# PGTNX07_gate_out.net
KiCad netlist of a schematic drawn in EAGLE
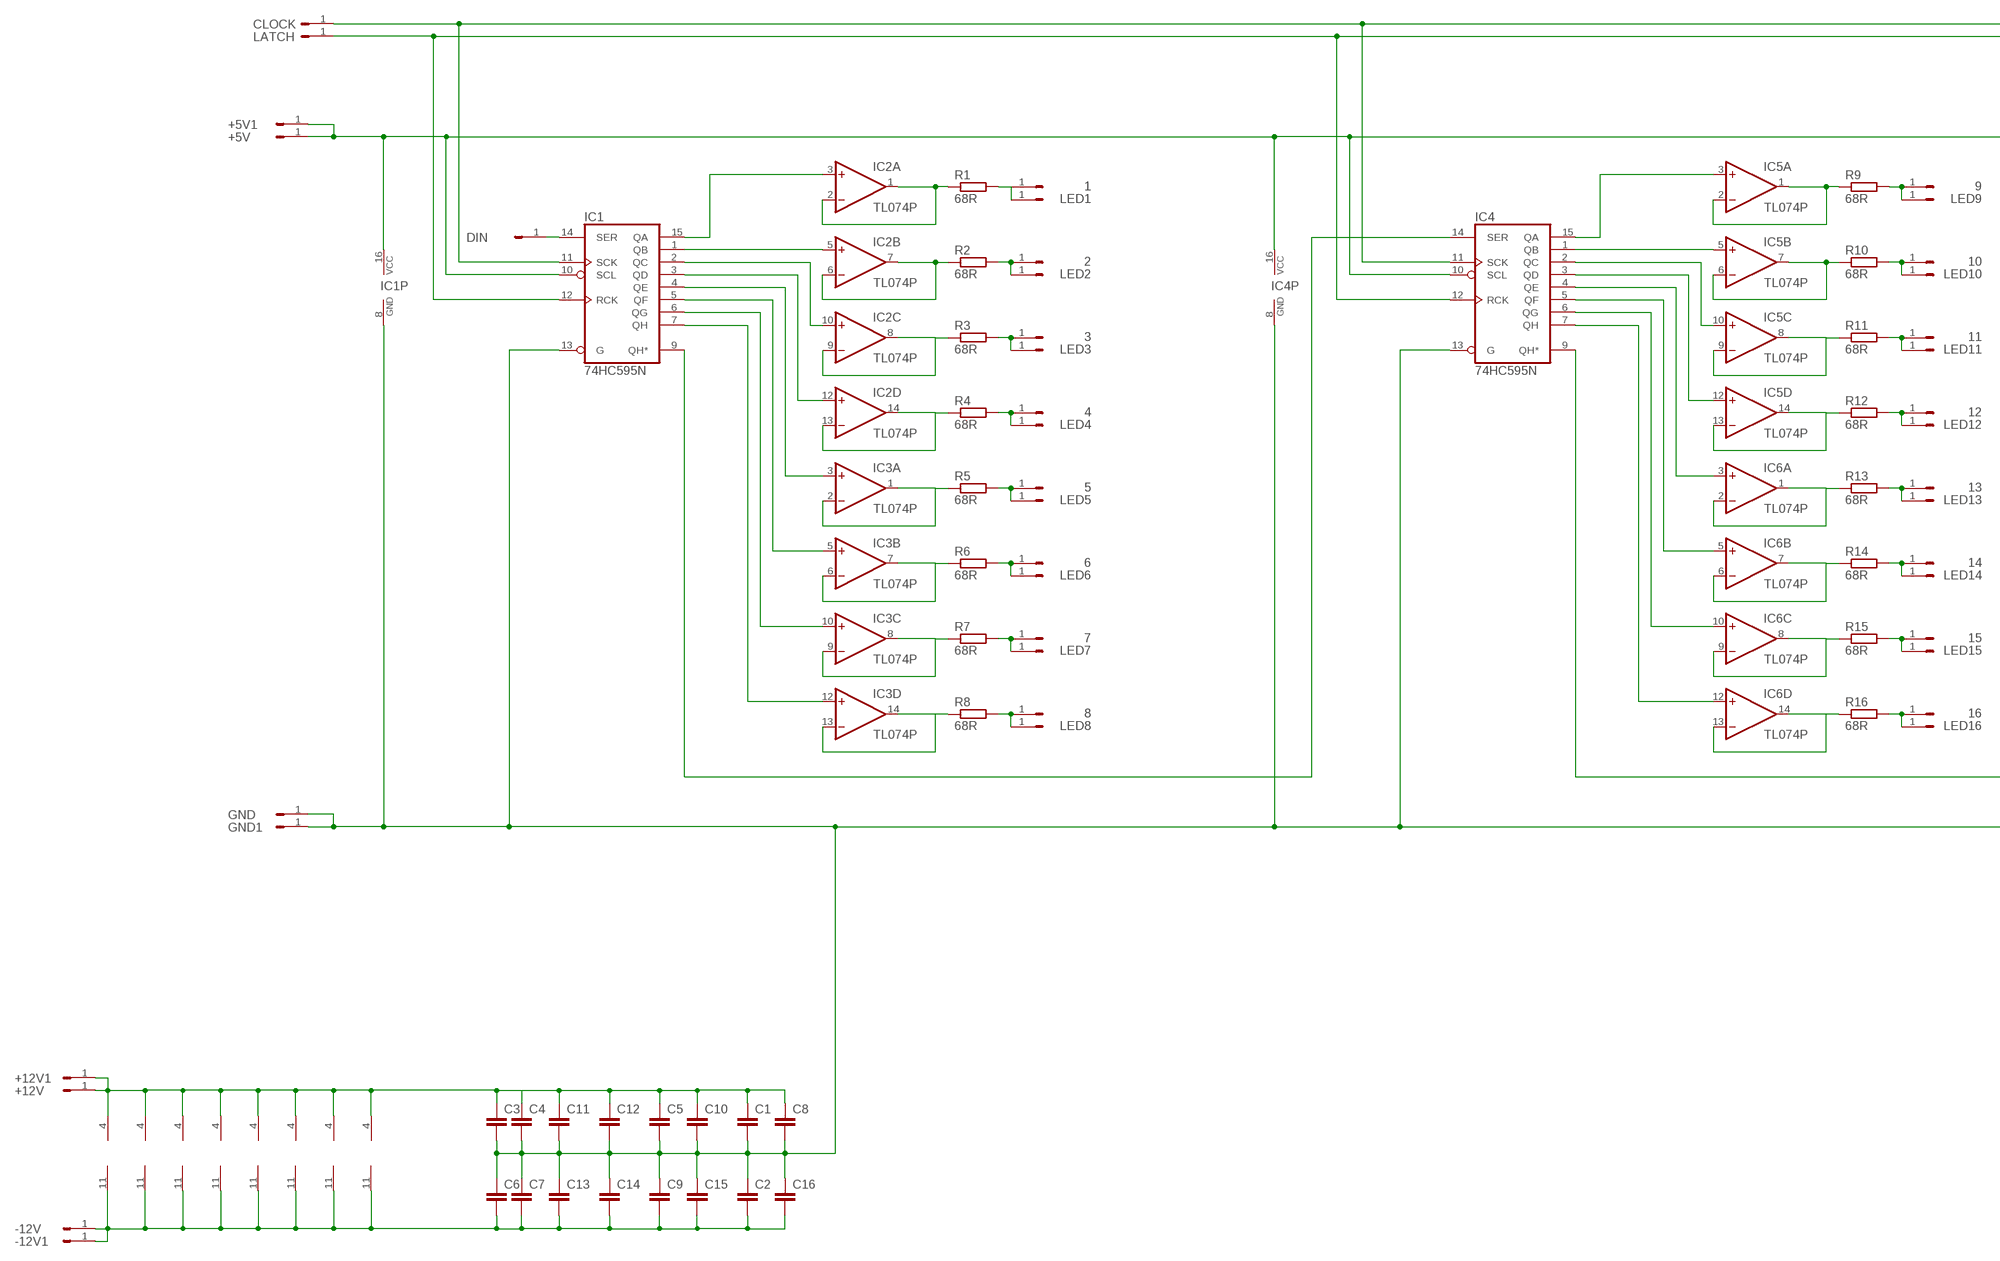
[diagram p0: schematic, sheet 1, part 1 of 2]
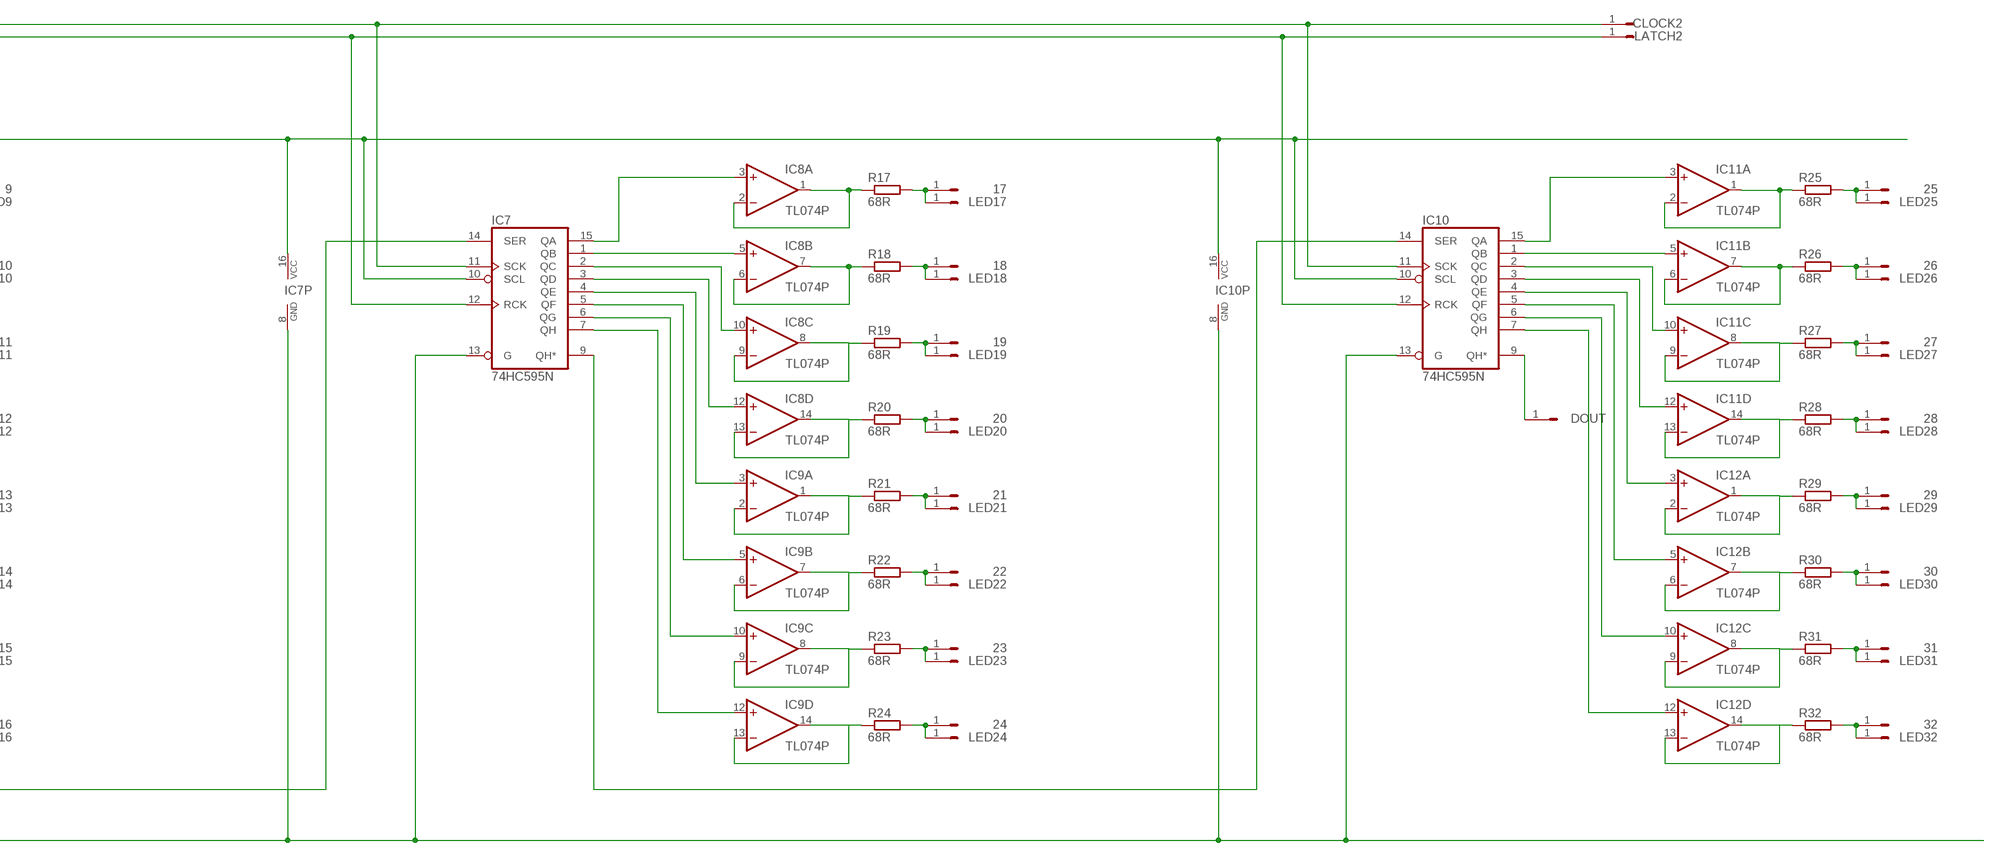
[diagram p1: schematic, sheet 1, part 2 of 2]

(export (version "E")
  (design (tool "Eeschema 10.0.6"))
  (components
    (comp (ref "+5V")
      (value "HEADER/MALE/01")
      (footprint "eagle-import:HEADER_MALE_01")
      (libsource (lib "eagle-import") (part "HEADER/MALE/01"))
    )
    (comp (ref "+5V1")
      (value "HEADER/MALE/01")
      (footprint "eagle-import:HEADER_MALE_01")
      (libsource (lib "eagle-import") (part "HEADER/MALE/01"))
    )
    (comp (ref "+12V")
      (value "HEADER/MALE/01")
      (footprint "eagle-import:HEADER_MALE_01")
      (libsource (lib "eagle-import") (part "HEADER/MALE/01"))
    )
    (comp (ref "+12V1")
      (value "HEADER/MALE/01")
      (footprint "eagle-import:HEADER_MALE_01")
      (libsource (lib "eagle-import") (part "HEADER/MALE/01"))
    )
    (comp (ref "-12V")
      (value "HEADER/MALE/01")
      (footprint "eagle-import:HEADER_MALE_01")
      (libsource (lib "eagle-import") (part "HEADER/MALE/01"))
    )
    (comp (ref "-12V1")
      (value "HEADER/MALE/01")
      (footprint "eagle-import:HEADER_MALE_01")
      (libsource (lib "eagle-import") (part "HEADER/MALE/01"))
    )
    (comp (ref "1")
      (value "HEADER/MALE/01")
      (footprint "eagle-import:HEADER_MALE_01")
      (libsource (lib "eagle-import") (part "HEADER/MALE/01"))
    )
    (comp (ref "2")
      (value "HEADER/MALE/01")
      (footprint "eagle-import:HEADER_MALE_01")
      (libsource (lib "eagle-import") (part "HEADER/MALE/01"))
    )
    (comp (ref "3")
      (value "HEADER/MALE/01")
      (footprint "eagle-import:HEADER_MALE_01")
      (libsource (lib "eagle-import") (part "HEADER/MALE/01"))
    )
    (comp (ref "4")
      (value "HEADER/MALE/01")
      (footprint "eagle-import:HEADER_MALE_01")
      (libsource (lib "eagle-import") (part "HEADER/MALE/01"))
    )
    (comp (ref "5")
      (value "HEADER/MALE/01")
      (footprint "eagle-import:HEADER_MALE_01")
      (libsource (lib "eagle-import") (part "HEADER/MALE/01"))
    )
    (comp (ref "6")
      (value "HEADER/MALE/01")
      (footprint "eagle-import:HEADER_MALE_01")
      (libsource (lib "eagle-import") (part "HEADER/MALE/01"))
    )
    (comp (ref "7")
      (value "HEADER/MALE/01")
      (footprint "eagle-import:HEADER_MALE_01")
      (libsource (lib "eagle-import") (part "HEADER/MALE/01"))
    )
    (comp (ref "8")
      (value "HEADER/MALE/01")
      (footprint "eagle-import:HEADER_MALE_01")
      (libsource (lib "eagle-import") (part "HEADER/MALE/01"))
    )
    (comp (ref "9")
      (value "HEADER/MALE/01")
      (footprint "eagle-import:HEADER_MALE_01")
      (libsource (lib "eagle-import") (part "HEADER/MALE/01"))
    )
    (comp (ref "10")
      (value "HEADER/MALE/01")
      (footprint "eagle-import:HEADER_MALE_01")
      (libsource (lib "eagle-import") (part "HEADER/MALE/01"))
    )
    (comp (ref "11")
      (value "HEADER/MALE/01")
      (footprint "eagle-import:HEADER_MALE_01")
      (libsource (lib "eagle-import") (part "HEADER/MALE/01"))
    )
    (comp (ref "12")
      (value "HEADER/MALE/01")
      (footprint "eagle-import:HEADER_MALE_01")
      (libsource (lib "eagle-import") (part "HEADER/MALE/01"))
    )
    (comp (ref "13")
      (value "HEADER/MALE/01")
      (footprint "eagle-import:HEADER_MALE_01")
      (libsource (lib "eagle-import") (part "HEADER/MALE/01"))
    )
    (comp (ref "14")
      (value "HEADER/MALE/01")
      (footprint "eagle-import:HEADER_MALE_01")
      (libsource (lib "eagle-import") (part "HEADER/MALE/01"))
    )
    (comp (ref "15")
      (value "HEADER/MALE/01")
      (footprint "eagle-import:HEADER_MALE_01")
      (libsource (lib "eagle-import") (part "HEADER/MALE/01"))
    )
    (comp (ref "16")
      (value "HEADER/MALE/01")
      (footprint "eagle-import:HEADER_MALE_01")
      (libsource (lib "eagle-import") (part "HEADER/MALE/01"))
    )
    (comp (ref "17")
      (value "HEADER/MALE/01")
      (footprint "eagle-import:HEADER_MALE_01")
      (libsource (lib "eagle-import") (part "HEADER/MALE/01"))
    )
    (comp (ref "18")
      (value "HEADER/MALE/01")
      (footprint "eagle-import:HEADER_MALE_01")
      (libsource (lib "eagle-import") (part "HEADER/MALE/01"))
    )
    (comp (ref "19")
      (value "HEADER/MALE/01")
      (footprint "eagle-import:HEADER_MALE_01")
      (libsource (lib "eagle-import") (part "HEADER/MALE/01"))
    )
    (comp (ref "20")
      (value "HEADER/MALE/01")
      (footprint "eagle-import:HEADER_MALE_01")
      (libsource (lib "eagle-import") (part "HEADER/MALE/01"))
    )
    (comp (ref "21")
      (value "HEADER/MALE/01")
      (footprint "eagle-import:HEADER_MALE_01")
      (libsource (lib "eagle-import") (part "HEADER/MALE/01"))
    )
    (comp (ref "22")
      (value "HEADER/MALE/01")
      (footprint "eagle-import:HEADER_MALE_01")
      (libsource (lib "eagle-import") (part "HEADER/MALE/01"))
    )
    (comp (ref "23")
      (value "HEADER/MALE/01")
      (footprint "eagle-import:HEADER_MALE_01")
      (libsource (lib "eagle-import") (part "HEADER/MALE/01"))
    )
    (comp (ref "24")
      (value "HEADER/MALE/01")
      (footprint "eagle-import:HEADER_MALE_01")
      (libsource (lib "eagle-import") (part "HEADER/MALE/01"))
    )
    (comp (ref "25")
      (value "HEADER/MALE/01")
      (footprint "eagle-import:HEADER_MALE_01")
      (libsource (lib "eagle-import") (part "HEADER/MALE/01"))
    )
    (comp (ref "26")
      (value "HEADER/MALE/01")
      (footprint "eagle-import:HEADER_MALE_01")
      (libsource (lib "eagle-import") (part "HEADER/MALE/01"))
    )
    (comp (ref "27")
      (value "HEADER/MALE/01")
      (footprint "eagle-import:HEADER_MALE_01")
      (libsource (lib "eagle-import") (part "HEADER/MALE/01"))
    )
    (comp (ref "28")
      (value "HEADER/MALE/01")
      (footprint "eagle-import:HEADER_MALE_01")
      (libsource (lib "eagle-import") (part "HEADER/MALE/01"))
    )
    (comp (ref "29")
      (value "HEADER/MALE/01")
      (footprint "eagle-import:HEADER_MALE_01")
      (libsource (lib "eagle-import") (part "HEADER/MALE/01"))
    )
    (comp (ref "30")
      (value "HEADER/MALE/01")
      (footprint "eagle-import:HEADER_MALE_01")
      (libsource (lib "eagle-import") (part "HEADER/MALE/01"))
    )
    (comp (ref "31")
      (value "HEADER/MALE/01")
      (footprint "eagle-import:HEADER_MALE_01")
      (libsource (lib "eagle-import") (part "HEADER/MALE/01"))
    )
    (comp (ref "32")
      (value "HEADER/MALE/01")
      (footprint "eagle-import:HEADER_MALE_01")
      (libsource (lib "eagle-import") (part "HEADER/MALE/01"))
    )
    (comp (ref "C1")
      (value "CAPACITORCERAMICDISC/5")
      (footprint "eagle-import:CERAMICDISC_5")
      (libsource (lib "eagle-import") (part "CAPACITORCERAMICDISC/5"))
    )
    (comp (ref "C2")
      (value "CAPACITORCERAMICDISC/5")
      (footprint "eagle-import:CERAMICDISC_5")
      (libsource (lib "eagle-import") (part "CAPACITORCERAMICDISC/5"))
    )
    (comp (ref "C3")
      (value "CAPACITORCERAMICDISC/5")
      (footprint "eagle-import:CERAMICDISC_5")
      (libsource (lib "eagle-import") (part "CAPACITORCERAMICDISC/5"))
    )
    (comp (ref "C4")
      (value "CAPACITORCERAMICDISC/5")
      (footprint "eagle-import:CERAMICDISC_5")
      (libsource (lib "eagle-import") (part "CAPACITORCERAMICDISC/5"))
    )
    (comp (ref "C5")
      (value "CAPACITORCERAMICDISC/5")
      (footprint "eagle-import:CERAMICDISC_5")
      (libsource (lib "eagle-import") (part "CAPACITORCERAMICDISC/5"))
    )
    (comp (ref "C6")
      (value "CAPACITORCERAMICDISC/5")
      (footprint "eagle-import:CERAMICDISC_5")
      (libsource (lib "eagle-import") (part "CAPACITORCERAMICDISC/5"))
    )
    (comp (ref "C7")
      (value "CAPACITORCERAMICDISC/5")
      (footprint "eagle-import:CERAMICDISC_5")
      (libsource (lib "eagle-import") (part "CAPACITORCERAMICDISC/5"))
    )
    (comp (ref "C8")
      (value "CAPACITORCERAMICDISC/5")
      (footprint "eagle-import:CERAMICDISC_5")
      (libsource (lib "eagle-import") (part "CAPACITORCERAMICDISC/5"))
    )
    (comp (ref "C9")
      (value "CAPACITORCERAMICDISC/5")
      (footprint "eagle-import:CERAMICDISC_5")
      (libsource (lib "eagle-import") (part "CAPACITORCERAMICDISC/5"))
    )
    (comp (ref "C10")
      (value "CAPACITORCERAMICDISC/5")
      (footprint "eagle-import:CERAMICDISC_5")
      (libsource (lib "eagle-import") (part "CAPACITORCERAMICDISC/5"))
    )
    (comp (ref "C11")
      (value "CAPACITORCERAMICDISC/5")
      (footprint "eagle-import:CERAMICDISC_5")
      (libsource (lib "eagle-import") (part "CAPACITORCERAMICDISC/5"))
    )
    (comp (ref "C12")
      (value "CAPACITORCERAMICDISC/5")
      (footprint "eagle-import:CERAMICDISC_5")
      (libsource (lib "eagle-import") (part "CAPACITORCERAMICDISC/5"))
    )
    (comp (ref "C13")
      (value "CAPACITORCERAMICDISC/5")
      (footprint "eagle-import:CERAMICDISC_5")
      (libsource (lib "eagle-import") (part "CAPACITORCERAMICDISC/5"))
    )
    (comp (ref "C14")
      (value "CAPACITORCERAMICDISC/5")
      (footprint "eagle-import:CERAMICDISC_5")
      (libsource (lib "eagle-import") (part "CAPACITORCERAMICDISC/5"))
    )
    (comp (ref "C15")
      (value "CAPACITORCERAMICDISC/5")
      (footprint "eagle-import:CERAMICDISC_5")
      (libsource (lib "eagle-import") (part "CAPACITORCERAMICDISC/5"))
    )
    (comp (ref "C16")
      (value "CAPACITORCERAMICDISC/5")
      (footprint "eagle-import:CERAMICDISC_5")
      (libsource (lib "eagle-import") (part "CAPACITORCERAMICDISC/5"))
    )
    (comp (ref "CLOCK")
      (value "HEADER/MALE/01")
      (footprint "eagle-import:HEADER_MALE_01")
      (libsource (lib "eagle-import") (part "HEADER/MALE/01"))
    )
    (comp (ref "CLOCK2")
      (value "HEADER/MALE/01")
      (footprint "eagle-import:HEADER_MALE_01")
      (libsource (lib "eagle-import") (part "HEADER/MALE/01"))
    )
    (comp (ref "DIN")
      (value "HEADER/MALE/01")
      (footprint "eagle-import:HEADER_MALE_01")
      (libsource (lib "eagle-import") (part "HEADER/MALE/01"))
    )
    (comp (ref "DOUT")
      (value "HEADER/MALE/01")
      (footprint "eagle-import:HEADER_MALE_01")
      (libsource (lib "eagle-import") (part "HEADER/MALE/01"))
    )
    (comp (ref "GND")
      (value "HEADER/MALE/01")
      (footprint "eagle-import:HEADER_MALE_01")
      (libsource (lib "eagle-import") (part "HEADER/MALE/01"))
    )
    (comp (ref "GND1")
      (value "HEADER/MALE/01")
      (footprint "eagle-import:HEADER_MALE_01")
      (libsource (lib "eagle-import") (part "HEADER/MALE/01"))
    )
    (comp (ref "IC1")
      (value "74HC595N")
      (footprint "eagle-import:DIL16")
      (libsource (lib "eagle-import") (part "74595NHC"))
    )
    (comp (ref "IC2")
      (value "TL074P")
      (footprint "eagle-import:DIL14")
      (libsource (lib "eagle-import") (part "TL074P"))
    )
    (comp (ref "IC3")
      (value "TL074P")
      (footprint "eagle-import:DIL14")
      (libsource (lib "eagle-import") (part "TL074P"))
    )
    (comp (ref "IC4")
      (value "74HC595N")
      (footprint "eagle-import:DIL16")
      (libsource (lib "eagle-import") (part "74595NHC"))
    )
    (comp (ref "IC5")
      (value "TL074P")
      (footprint "eagle-import:DIL14")
      (libsource (lib "eagle-import") (part "TL074P"))
    )
    (comp (ref "IC6")
      (value "TL074P")
      (footprint "eagle-import:DIL14")
      (libsource (lib "eagle-import") (part "TL074P"))
    )
    (comp (ref "IC7")
      (value "74HC595N")
      (footprint "eagle-import:DIL16")
      (libsource (lib "eagle-import") (part "74595NHC"))
    )
    (comp (ref "IC8")
      (value "TL074P")
      (footprint "eagle-import:DIL14")
      (libsource (lib "eagle-import") (part "TL074P"))
    )
    (comp (ref "IC9")
      (value "TL074P")
      (footprint "eagle-import:DIL14")
      (libsource (lib "eagle-import") (part "TL074P"))
    )
    (comp (ref "IC10")
      (value "74HC595N")
      (footprint "eagle-import:DIL16")
      (libsource (lib "eagle-import") (part "74595NHC"))
    )
    (comp (ref "IC11")
      (value "TL074P")
      (footprint "eagle-import:DIL14")
      (libsource (lib "eagle-import") (part "TL074P"))
    )
    (comp (ref "IC12")
      (value "TL074P")
      (footprint "eagle-import:DIL14")
      (libsource (lib "eagle-import") (part "TL074P"))
    )
    (comp (ref "LATCH")
      (value "HEADER/MALE/01")
      (footprint "eagle-import:HEADER_MALE_01")
      (libsource (lib "eagle-import") (part "HEADER/MALE/01"))
    )
    (comp (ref "LATCH2")
      (value "HEADER/MALE/01")
      (footprint "eagle-import:HEADER_MALE_01")
      (libsource (lib "eagle-import") (part "HEADER/MALE/01"))
    )
    (comp (ref "LED1")
      (value "HEADER/MALE/01")
      (footprint "eagle-import:HEADER_MALE_01")
      (libsource (lib "eagle-import") (part "HEADER/MALE/01"))
    )
    (comp (ref "LED2")
      (value "HEADER/MALE/01")
      (footprint "eagle-import:HEADER_MALE_01")
      (libsource (lib "eagle-import") (part "HEADER/MALE/01"))
    )
    (comp (ref "LED3")
      (value "HEADER/MALE/01")
      (footprint "eagle-import:HEADER_MALE_01")
      (libsource (lib "eagle-import") (part "HEADER/MALE/01"))
    )
    (comp (ref "LED4")
      (value "HEADER/MALE/01")
      (footprint "eagle-import:HEADER_MALE_01")
      (libsource (lib "eagle-import") (part "HEADER/MALE/01"))
    )
    (comp (ref "LED5")
      (value "HEADER/MALE/01")
      (footprint "eagle-import:HEADER_MALE_01")
      (libsource (lib "eagle-import") (part "HEADER/MALE/01"))
    )
    (comp (ref "LED6")
      (value "HEADER/MALE/01")
      (footprint "eagle-import:HEADER_MALE_01")
      (libsource (lib "eagle-import") (part "HEADER/MALE/01"))
    )
    (comp (ref "LED7")
      (value "HEADER/MALE/01")
      (footprint "eagle-import:HEADER_MALE_01")
      (libsource (lib "eagle-import") (part "HEADER/MALE/01"))
    )
    (comp (ref "LED8")
      (value "HEADER/MALE/01")
      (footprint "eagle-import:HEADER_MALE_01")
      (libsource (lib "eagle-import") (part "HEADER/MALE/01"))
    )
    (comp (ref "LED9")
      (value "HEADER/MALE/01")
      (footprint "eagle-import:HEADER_MALE_01")
      (libsource (lib "eagle-import") (part "HEADER/MALE/01"))
    )
    (comp (ref "LED10")
      (value "HEADER/MALE/01")
      (footprint "eagle-import:HEADER_MALE_01")
      (libsource (lib "eagle-import") (part "HEADER/MALE/01"))
    )
    (comp (ref "LED11")
      (value "HEADER/MALE/01")
      (footprint "eagle-import:HEADER_MALE_01")
      (libsource (lib "eagle-import") (part "HEADER/MALE/01"))
    )
    (comp (ref "LED12")
      (value "HEADER/MALE/01")
      (footprint "eagle-import:HEADER_MALE_01")
      (libsource (lib "eagle-import") (part "HEADER/MALE/01"))
    )
    (comp (ref "LED13")
      (value "HEADER/MALE/01")
      (footprint "eagle-import:HEADER_MALE_01")
      (libsource (lib "eagle-import") (part "HEADER/MALE/01"))
    )
    (comp (ref "LED14")
      (value "HEADER/MALE/01")
      (footprint "eagle-import:HEADER_MALE_01")
      (libsource (lib "eagle-import") (part "HEADER/MALE/01"))
    )
    (comp (ref "LED15")
      (value "HEADER/MALE/01")
      (footprint "eagle-import:HEADER_MALE_01")
      (libsource (lib "eagle-import") (part "HEADER/MALE/01"))
    )
    (comp (ref "LED16")
      (value "HEADER/MALE/01")
      (footprint "eagle-import:HEADER_MALE_01")
      (libsource (lib "eagle-import") (part "HEADER/MALE/01"))
    )
    (comp (ref "LED17")
      (value "HEADER/MALE/01")
      (footprint "eagle-import:HEADER_MALE_01")
      (libsource (lib "eagle-import") (part "HEADER/MALE/01"))
    )
    (comp (ref "LED18")
      (value "HEADER/MALE/01")
      (footprint "eagle-import:HEADER_MALE_01")
      (libsource (lib "eagle-import") (part "HEADER/MALE/01"))
    )
    (comp (ref "LED19")
      (value "HEADER/MALE/01")
      (footprint "eagle-import:HEADER_MALE_01")
      (libsource (lib "eagle-import") (part "HEADER/MALE/01"))
    )
    (comp (ref "LED20")
      (value "HEADER/MALE/01")
      (footprint "eagle-import:HEADER_MALE_01")
      (libsource (lib "eagle-import") (part "HEADER/MALE/01"))
    )
    (comp (ref "LED21")
      (value "HEADER/MALE/01")
      (footprint "eagle-import:HEADER_MALE_01")
      (libsource (lib "eagle-import") (part "HEADER/MALE/01"))
    )
    (comp (ref "LED22")
      (value "HEADER/MALE/01")
      (footprint "eagle-import:HEADER_MALE_01")
      (libsource (lib "eagle-import") (part "HEADER/MALE/01"))
    )
    (comp (ref "LED23")
      (value "HEADER/MALE/01")
      (footprint "eagle-import:HEADER_MALE_01")
      (libsource (lib "eagle-import") (part "HEADER/MALE/01"))
    )
    (comp (ref "LED24")
      (value "HEADER/MALE/01")
      (footprint "eagle-import:HEADER_MALE_01")
      (libsource (lib "eagle-import") (part "HEADER/MALE/01"))
    )
    (comp (ref "LED25")
      (value "HEADER/MALE/01")
      (footprint "eagle-import:HEADER_MALE_01")
      (libsource (lib "eagle-import") (part "HEADER/MALE/01"))
    )
    (comp (ref "LED26")
      (value "HEADER/MALE/01")
      (footprint "eagle-import:HEADER_MALE_01")
      (libsource (lib "eagle-import") (part "HEADER/MALE/01"))
    )
    (comp (ref "LED27")
      (value "HEADER/MALE/01")
      (footprint "eagle-import:HEADER_MALE_01")
      (libsource (lib "eagle-import") (part "HEADER/MALE/01"))
    )
    (comp (ref "LED28")
      (value "HEADER/MALE/01")
      (footprint "eagle-import:HEADER_MALE_01")
      (libsource (lib "eagle-import") (part "HEADER/MALE/01"))
    )
    (comp (ref "LED29")
      (value "HEADER/MALE/01")
      (footprint "eagle-import:HEADER_MALE_01")
      (libsource (lib "eagle-import") (part "HEADER/MALE/01"))
    )
    (comp (ref "LED30")
      (value "HEADER/MALE/01")
      (footprint "eagle-import:HEADER_MALE_01")
      (libsource (lib "eagle-import") (part "HEADER/MALE/01"))
    )
    (comp (ref "LED31")
      (value "HEADER/MALE/01")
      (footprint "eagle-import:HEADER_MALE_01")
      (libsource (lib "eagle-import") (part "HEADER/MALE/01"))
    )
    (comp (ref "LED32")
      (value "HEADER/MALE/01")
      (footprint "eagle-import:HEADER_MALE_01")
      (libsource (lib "eagle-import") (part "HEADER/MALE/01"))
    )
    (comp (ref "R1")
      (value "68R")
      (footprint "eagle-import:RESISTOR_7.5")
      (libsource (lib "eagle-import") (part "RESISTORRESISTOR/UPRIGHT/7.5"))
    )
    (comp (ref "R2")
      (value "68R")
      (footprint "eagle-import:RESISTOR_7.5")
      (libsource (lib "eagle-import") (part "RESISTORRESISTOR/UPRIGHT/7.5"))
    )
    (comp (ref "R3")
      (value "68R")
      (footprint "eagle-import:RESISTOR_7.5")
      (libsource (lib "eagle-import") (part "RESISTORRESISTOR/UPRIGHT/7.5"))
    )
    (comp (ref "R4")
      (value "68R")
      (footprint "eagle-import:RESISTOR_7.5")
      (libsource (lib "eagle-import") (part "RESISTORRESISTOR/UPRIGHT/7.5"))
    )
    (comp (ref "R5")
      (value "68R")
      (footprint "eagle-import:RESISTOR_7.5")
      (libsource (lib "eagle-import") (part "RESISTORRESISTOR/UPRIGHT/7.5"))
    )
    (comp (ref "R6")
      (value "68R")
      (footprint "eagle-import:RESISTOR_7.5")
      (libsource (lib "eagle-import") (part "RESISTORRESISTOR/UPRIGHT/7.5"))
    )
    (comp (ref "R7")
      (value "68R")
      (footprint "eagle-import:RESISTOR_7.5")
      (libsource (lib "eagle-import") (part "RESISTORRESISTOR/UPRIGHT/7.5"))
    )
    (comp (ref "R8")
      (value "68R")
      (footprint "eagle-import:RESISTOR_7.5")
      (libsource (lib "eagle-import") (part "RESISTORRESISTOR/UPRIGHT/7.5"))
    )
    (comp (ref "R9")
      (value "68R")
      (footprint "eagle-import:RESISTOR_7.5")
      (libsource (lib "eagle-import") (part "RESISTORRESISTOR/UPRIGHT/7.5"))
    )
    (comp (ref "R10")
      (value "68R")
      (footprint "eagle-import:RESISTOR_7.5")
      (libsource (lib "eagle-import") (part "RESISTORRESISTOR/UPRIGHT/7.5"))
    )
    (comp (ref "R11")
      (value "68R")
      (footprint "eagle-import:RESISTOR_7.5")
      (libsource (lib "eagle-import") (part "RESISTORRESISTOR/UPRIGHT/7.5"))
    )
    (comp (ref "R12")
      (value "68R")
      (footprint "eagle-import:RESISTOR_7.5")
      (libsource (lib "eagle-import") (part "RESISTORRESISTOR/UPRIGHT/7.5"))
    )
    (comp (ref "R13")
      (value "68R")
      (footprint "eagle-import:RESISTOR_7.5")
      (libsource (lib "eagle-import") (part "RESISTORRESISTOR/UPRIGHT/7.5"))
    )
    (comp (ref "R14")
      (value "68R")
      (footprint "eagle-import:RESISTOR_7.5")
      (libsource (lib "eagle-import") (part "RESISTORRESISTOR/UPRIGHT/7.5"))
    )
    (comp (ref "R15")
      (value "68R")
      (footprint "eagle-import:RESISTOR_7.5")
      (libsource (lib "eagle-import") (part "RESISTORRESISTOR/UPRIGHT/7.5"))
    )
    (comp (ref "R16")
      (value "68R")
      (footprint "eagle-import:RESISTOR_7.5")
      (libsource (lib "eagle-import") (part "RESISTORRESISTOR/UPRIGHT/7.5"))
    )
    (comp (ref "R17")
      (value "68R")
      (footprint "eagle-import:RESISTOR_7.5")
      (libsource (lib "eagle-import") (part "RESISTORRESISTOR/UPRIGHT/7.5"))
    )
    (comp (ref "R18")
      (value "68R")
      (footprint "eagle-import:RESISTOR_7.5")
      (libsource (lib "eagle-import") (part "RESISTORRESISTOR/UPRIGHT/7.5"))
    )
    (comp (ref "R19")
      (value "68R")
      (footprint "eagle-import:RESISTOR_7.5")
      (libsource (lib "eagle-import") (part "RESISTORRESISTOR/UPRIGHT/7.5"))
    )
    (comp (ref "R20")
      (value "68R")
      (footprint "eagle-import:RESISTOR_7.5")
      (libsource (lib "eagle-import") (part "RESISTORRESISTOR/UPRIGHT/7.5"))
    )
    (comp (ref "R21")
      (value "68R")
      (footprint "eagle-import:RESISTOR_7.5")
      (libsource (lib "eagle-import") (part "RESISTORRESISTOR/UPRIGHT/7.5"))
    )
    (comp (ref "R22")
      (value "68R")
      (footprint "eagle-import:RESISTOR_7.5")
      (libsource (lib "eagle-import") (part "RESISTORRESISTOR/UPRIGHT/7.5"))
    )
    (comp (ref "R23")
      (value "68R")
      (footprint "eagle-import:RESISTOR_7.5")
      (libsource (lib "eagle-import") (part "RESISTORRESISTOR/UPRIGHT/7.5"))
    )
    (comp (ref "R24")
      (value "68R")
      (footprint "eagle-import:RESISTOR_7.5")
      (libsource (lib "eagle-import") (part "RESISTORRESISTOR/UPRIGHT/7.5"))
    )
    (comp (ref "R25")
      (value "68R")
      (footprint "eagle-import:RESISTOR_7.5")
      (libsource (lib "eagle-import") (part "RESISTORRESISTOR/UPRIGHT/7.5"))
    )
    (comp (ref "R26")
      (value "68R")
      (footprint "eagle-import:RESISTOR_7.5")
      (libsource (lib "eagle-import") (part "RESISTORRESISTOR/UPRIGHT/7.5"))
    )
    (comp (ref "R27")
      (value "68R")
      (footprint "eagle-import:RESISTOR_7.5")
      (libsource (lib "eagle-import") (part "RESISTORRESISTOR/UPRIGHT/7.5"))
    )
    (comp (ref "R28")
      (value "68R")
      (footprint "eagle-import:RESISTOR_7.5")
      (libsource (lib "eagle-import") (part "RESISTORRESISTOR/UPRIGHT/7.5"))
    )
    (comp (ref "R29")
      (value "68R")
      (footprint "eagle-import:RESISTOR_7.5")
      (libsource (lib "eagle-import") (part "RESISTORRESISTOR/UPRIGHT/7.5"))
    )
    (comp (ref "R30")
      (value "68R")
      (footprint "eagle-import:RESISTOR_7.5")
      (libsource (lib "eagle-import") (part "RESISTORRESISTOR/UPRIGHT/7.5"))
    )
    (comp (ref "R31")
      (value "68R")
      (footprint "eagle-import:RESISTOR_7.5")
      (libsource (lib "eagle-import") (part "RESISTORRESISTOR/UPRIGHT/7.5"))
    )
    (comp (ref "R32")
      (value "68R")
      (footprint "eagle-import:RESISTOR_7.5")
      (libsource (lib "eagle-import") (part "RESISTORRESISTOR/UPRIGHT/7.5"))
    )
  )
  (nets
    (net (code "1") (name "Net-(+5V-3)") (class "Default")
      (node (ref "+5V") (pin "1") (pinfunction "3_1") (pintype "passive"))
      (node (ref "+5V1") (pin "1") (pinfunction "3_1") (pintype "passive"))
      (node (ref "IC1") (pin "10") (pinfunction "SCL_10") (pintype "input"))
      (node (ref "IC1") (pin "16") (pinfunction "VCC_16") (pintype "power_in"))
      (node (ref "IC10") (pin "10") (pinfunction "SCL_10") (pintype "input"))
      (node (ref "IC10") (pin "16") (pinfunction "VCC_16") (pintype "power_in"))
      (node (ref "IC4") (pin "10") (pinfunction "SCL_10") (pintype "input"))
      (node (ref "IC4") (pin "16") (pinfunction "VCC_16") (pintype "power_in"))
      (node (ref "IC7") (pin "10") (pinfunction "SCL_10") (pintype "input"))
      (node (ref "IC7") (pin "16") (pinfunction "VCC_16") (pintype "power_in"))
    )
    (net (code "2") (name "Net-(+12V-3)") (class "Default")
      (node (ref "+12V") (pin "1") (pinfunction "3_1") (pintype "passive"))
      (node (ref "+12V1") (pin "1") (pinfunction "3_1") (pintype "passive"))
      (node (ref "C1") (pin "1") (pinfunction "1_1") (pintype "passive"))
      (node (ref "C10") (pin "1") (pinfunction "1_1") (pintype "passive"))
      (node (ref "C11") (pin "1") (pinfunction "1_1") (pintype "passive"))
      (node (ref "C12") (pin "1") (pinfunction "1_1") (pintype "passive"))
      (node (ref "C3") (pin "1") (pinfunction "1_1") (pintype "passive"))
      (node (ref "C4") (pin "1") (pinfunction "1_1") (pintype "passive"))
      (node (ref "C5") (pin "1") (pinfunction "1_1") (pintype "passive"))
      (node (ref "C8") (pin "1") (pinfunction "1_1") (pintype "passive"))
      (node (ref "IC11") (pin "4") (pinfunction "V+_4") (pintype "power_in"))
      (node (ref "IC12") (pin "4") (pinfunction "V+_4") (pintype "power_in"))
      (node (ref "IC2") (pin "4") (pinfunction "V+_4") (pintype "power_in"))
      (node (ref "IC3") (pin "4") (pinfunction "V+_4") (pintype "power_in"))
      (node (ref "IC5") (pin "4") (pinfunction "V+_4") (pintype "power_in"))
      (node (ref "IC6") (pin "4") (pinfunction "V+_4") (pintype "power_in"))
      (node (ref "IC8") (pin "4") (pinfunction "V+_4") (pintype "power_in"))
      (node (ref "IC9") (pin "4") (pinfunction "V+_4") (pintype "power_in"))
    )
    (net (code "3") (name "Net-(-12V-3)") (class "Default")
      (node (ref "-12V") (pin "1") (pinfunction "3_1") (pintype "passive"))
      (node (ref "-12V1") (pin "1") (pinfunction "3_1") (pintype "passive"))
      (node (ref "C13") (pin "2") (pinfunction "2_2") (pintype "passive"))
      (node (ref "C14") (pin "2") (pinfunction "2_2") (pintype "passive"))
      (node (ref "C15") (pin "2") (pinfunction "2_2") (pintype "passive"))
      (node (ref "C16") (pin "2") (pinfunction "2_2") (pintype "passive"))
      (node (ref "C2") (pin "2") (pinfunction "2_2") (pintype "passive"))
      (node (ref "C6") (pin "2") (pinfunction "2_2") (pintype "passive"))
      (node (ref "C7") (pin "2") (pinfunction "2_2") (pintype "passive"))
      (node (ref "C9") (pin "2") (pinfunction "2_2") (pintype "passive"))
      (node (ref "IC11") (pin "11") (pinfunction "V-_11") (pintype "power_in"))
      (node (ref "IC12") (pin "11") (pinfunction "V-_11") (pintype "power_in"))
      (node (ref "IC2") (pin "11") (pinfunction "V-_11") (pintype "power_in"))
      (node (ref "IC3") (pin "11") (pinfunction "V-_11") (pintype "power_in"))
      (node (ref "IC5") (pin "11") (pinfunction "V-_11") (pintype "power_in"))
      (node (ref "IC6") (pin "11") (pinfunction "V-_11") (pintype "power_in"))
      (node (ref "IC8") (pin "11") (pinfunction "V-_11") (pintype "power_in"))
      (node (ref "IC9") (pin "11") (pinfunction "V-_11") (pintype "power_in"))
    )
    (net (code "4") (name "Net-(1-3)") (class "Default")
      (node (ref "1") (pin "1") (pinfunction "3_1") (pintype "passive"))
      (node (ref "LED1") (pin "1") (pinfunction "3_1") (pintype "passive"))
      (node (ref "R1") (pin "2") (pinfunction "2_2") (pintype "passive"))
    )
    (net (code "5") (name "Net-(2-3)") (class "Default")
      (node (ref "2") (pin "1") (pinfunction "3_1") (pintype "passive"))
      (node (ref "LED2") (pin "1") (pinfunction "3_1") (pintype "passive"))
      (node (ref "R2") (pin "2") (pinfunction "2_2") (pintype "passive"))
    )
    (net (code "6") (name "Net-(3-3)") (class "Default")
      (node (ref "3") (pin "1") (pinfunction "3_1") (pintype "passive"))
      (node (ref "LED3") (pin "1") (pinfunction "3_1") (pintype "passive"))
      (node (ref "R3") (pin "2") (pinfunction "2_2") (pintype "passive"))
    )
    (net (code "7") (name "Net-(4-3)") (class "Default")
      (node (ref "4") (pin "1") (pinfunction "3_1") (pintype "passive"))
      (node (ref "LED4") (pin "1") (pinfunction "3_1") (pintype "passive"))
      (node (ref "R4") (pin "2") (pinfunction "2_2") (pintype "passive"))
    )
    (net (code "8") (name "Net-(5-3)") (class "Default")
      (node (ref "5") (pin "1") (pinfunction "3_1") (pintype "passive"))
      (node (ref "LED5") (pin "1") (pinfunction "3_1") (pintype "passive"))
      (node (ref "R5") (pin "2") (pinfunction "2_2") (pintype "passive"))
    )
    (net (code "9") (name "Net-(6-3)") (class "Default")
      (node (ref "6") (pin "1") (pinfunction "3_1") (pintype "passive"))
      (node (ref "LED6") (pin "1") (pinfunction "3_1") (pintype "passive"))
      (node (ref "R6") (pin "2") (pinfunction "2_2") (pintype "passive"))
    )
    (net (code "10") (name "Net-(7-3)") (class "Default")
      (node (ref "7") (pin "1") (pinfunction "3_1") (pintype "passive"))
      (node (ref "LED7") (pin "1") (pinfunction "3_1") (pintype "passive"))
      (node (ref "R7") (pin "2") (pinfunction "2_2") (pintype "passive"))
    )
    (net (code "11") (name "Net-(8-3)") (class "Default")
      (node (ref "8") (pin "1") (pinfunction "3_1") (pintype "passive"))
      (node (ref "LED8") (pin "1") (pinfunction "3_1") (pintype "passive"))
      (node (ref "R8") (pin "2") (pinfunction "2_2") (pintype "passive"))
    )
    (net (code "12") (name "Net-(9-3)") (class "Default")
      (node (ref "9") (pin "1") (pinfunction "3_1") (pintype "passive"))
      (node (ref "LED9") (pin "1") (pinfunction "3_1") (pintype "passive"))
      (node (ref "R9") (pin "2") (pinfunction "2_2") (pintype "passive"))
    )
    (net (code "13") (name "Net-(10-3)") (class "Default")
      (node (ref "10") (pin "1") (pinfunction "3_1") (pintype "passive"))
      (node (ref "LED10") (pin "1") (pinfunction "3_1") (pintype "passive"))
      (node (ref "R10") (pin "2") (pinfunction "2_2") (pintype "passive"))
    )
    (net (code "14") (name "Net-(11-3)") (class "Default")
      (node (ref "11") (pin "1") (pinfunction "3_1") (pintype "passive"))
      (node (ref "LED11") (pin "1") (pinfunction "3_1") (pintype "passive"))
      (node (ref "R11") (pin "2") (pinfunction "2_2") (pintype "passive"))
    )
    (net (code "15") (name "Net-(12-3)") (class "Default")
      (node (ref "12") (pin "1") (pinfunction "3_1") (pintype "passive"))
      (node (ref "LED12") (pin "1") (pinfunction "3_1") (pintype "passive"))
      (node (ref "R12") (pin "2") (pinfunction "2_2") (pintype "passive"))
    )
    (net (code "16") (name "Net-(13-3)") (class "Default")
      (node (ref "13") (pin "1") (pinfunction "3_1") (pintype "passive"))
      (node (ref "LED13") (pin "1") (pinfunction "3_1") (pintype "passive"))
      (node (ref "R13") (pin "2") (pinfunction "2_2") (pintype "passive"))
    )
    (net (code "17") (name "Net-(14-3)") (class "Default")
      (node (ref "14") (pin "1") (pinfunction "3_1") (pintype "passive"))
      (node (ref "LED14") (pin "1") (pinfunction "3_1") (pintype "passive"))
      (node (ref "R14") (pin "2") (pinfunction "2_2") (pintype "passive"))
    )
    (net (code "18") (name "Net-(15-3)") (class "Default")
      (node (ref "15") (pin "1") (pinfunction "3_1") (pintype "passive"))
      (node (ref "LED15") (pin "1") (pinfunction "3_1") (pintype "passive"))
      (node (ref "R15") (pin "2") (pinfunction "2_2") (pintype "passive"))
    )
    (net (code "19") (name "Net-(16-3)") (class "Default")
      (node (ref "16") (pin "1") (pinfunction "3_1") (pintype "passive"))
      (node (ref "LED16") (pin "1") (pinfunction "3_1") (pintype "passive"))
      (node (ref "R16") (pin "2") (pinfunction "2_2") (pintype "passive"))
    )
    (net (code "20") (name "Net-(17-3)") (class "Default")
      (node (ref "17") (pin "1") (pinfunction "3_1") (pintype "passive"))
      (node (ref "LED17") (pin "1") (pinfunction "3_1") (pintype "passive"))
      (node (ref "R17") (pin "2") (pinfunction "2_2") (pintype "passive"))
    )
    (net (code "21") (name "Net-(18-3)") (class "Default")
      (node (ref "18") (pin "1") (pinfunction "3_1") (pintype "passive"))
      (node (ref "LED18") (pin "1") (pinfunction "3_1") (pintype "passive"))
      (node (ref "R18") (pin "2") (pinfunction "2_2") (pintype "passive"))
    )
    (net (code "22") (name "Net-(19-3)") (class "Default")
      (node (ref "19") (pin "1") (pinfunction "3_1") (pintype "passive"))
      (node (ref "LED19") (pin "1") (pinfunction "3_1") (pintype "passive"))
      (node (ref "R19") (pin "2") (pinfunction "2_2") (pintype "passive"))
    )
    (net (code "23") (name "Net-(20-3)") (class "Default")
      (node (ref "20") (pin "1") (pinfunction "3_1") (pintype "passive"))
      (node (ref "LED20") (pin "1") (pinfunction "3_1") (pintype "passive"))
      (node (ref "R20") (pin "2") (pinfunction "2_2") (pintype "passive"))
    )
    (net (code "24") (name "Net-(21-3)") (class "Default")
      (node (ref "21") (pin "1") (pinfunction "3_1") (pintype "passive"))
      (node (ref "LED21") (pin "1") (pinfunction "3_1") (pintype "passive"))
      (node (ref "R21") (pin "2") (pinfunction "2_2") (pintype "passive"))
    )
    (net (code "25") (name "Net-(22-3)") (class "Default")
      (node (ref "22") (pin "1") (pinfunction "3_1") (pintype "passive"))
      (node (ref "LED22") (pin "1") (pinfunction "3_1") (pintype "passive"))
      (node (ref "R22") (pin "2") (pinfunction "2_2") (pintype "passive"))
    )
    (net (code "26") (name "Net-(23-3)") (class "Default")
      (node (ref "23") (pin "1") (pinfunction "3_1") (pintype "passive"))
      (node (ref "LED23") (pin "1") (pinfunction "3_1") (pintype "passive"))
      (node (ref "R23") (pin "2") (pinfunction "2_2") (pintype "passive"))
    )
    (net (code "27") (name "Net-(24-3)") (class "Default")
      (node (ref "24") (pin "1") (pinfunction "3_1") (pintype "passive"))
      (node (ref "LED24") (pin "1") (pinfunction "3_1") (pintype "passive"))
      (node (ref "R24") (pin "2") (pinfunction "2_2") (pintype "passive"))
    )
    (net (code "28") (name "Net-(25-3)") (class "Default")
      (node (ref "25") (pin "1") (pinfunction "3_1") (pintype "passive"))
      (node (ref "LED25") (pin "1") (pinfunction "3_1") (pintype "passive"))
      (node (ref "R25") (pin "2") (pinfunction "2_2") (pintype "passive"))
    )
    (net (code "29") (name "Net-(26-3)") (class "Default")
      (node (ref "26") (pin "1") (pinfunction "3_1") (pintype "passive"))
      (node (ref "LED26") (pin "1") (pinfunction "3_1") (pintype "passive"))
      (node (ref "R26") (pin "2") (pinfunction "2_2") (pintype "passive"))
    )
    (net (code "30") (name "Net-(27-3)") (class "Default")
      (node (ref "27") (pin "1") (pinfunction "3_1") (pintype "passive"))
      (node (ref "LED27") (pin "1") (pinfunction "3_1") (pintype "passive"))
      (node (ref "R27") (pin "2") (pinfunction "2_2") (pintype "passive"))
    )
    (net (code "31") (name "Net-(28-3)") (class "Default")
      (node (ref "28") (pin "1") (pinfunction "3_1") (pintype "passive"))
      (node (ref "LED28") (pin "1") (pinfunction "3_1") (pintype "passive"))
      (node (ref "R28") (pin "2") (pinfunction "2_2") (pintype "passive"))
    )
    (net (code "32") (name "Net-(29-3)") (class "Default")
      (node (ref "29") (pin "1") (pinfunction "3_1") (pintype "passive"))
      (node (ref "LED29") (pin "1") (pinfunction "3_1") (pintype "passive"))
      (node (ref "R29") (pin "2") (pinfunction "2_2") (pintype "passive"))
    )
    (net (code "33") (name "Net-(30-3)") (class "Default")
      (node (ref "30") (pin "1") (pinfunction "3_1") (pintype "passive"))
      (node (ref "LED30") (pin "1") (pinfunction "3_1") (pintype "passive"))
      (node (ref "R30") (pin "2") (pinfunction "2_2") (pintype "passive"))
    )
    (net (code "34") (name "Net-(31-3)") (class "Default")
      (node (ref "31") (pin "1") (pinfunction "3_1") (pintype "passive"))
      (node (ref "LED31") (pin "1") (pinfunction "3_1") (pintype "passive"))
      (node (ref "R31") (pin "2") (pinfunction "2_2") (pintype "passive"))
    )
    (net (code "35") (name "Net-(32-3)") (class "Default")
      (node (ref "32") (pin "1") (pinfunction "3_1") (pintype "passive"))
      (node (ref "LED32") (pin "1") (pinfunction "3_1") (pintype "passive"))
      (node (ref "R32") (pin "2") (pinfunction "2_2") (pintype "passive"))
    )
    (net (code "36") (name "Net-(CLOCK-3)") (class "Default")
      (node (ref "CLOCK") (pin "1") (pinfunction "3_1") (pintype "passive"))
      (node (ref "CLOCK2") (pin "1") (pinfunction "3_1") (pintype "passive"))
      (node (ref "IC1") (pin "11") (pinfunction "SCK_11") (pintype "input"))
      (node (ref "IC10") (pin "11") (pinfunction "SCK_11") (pintype "input"))
      (node (ref "IC4") (pin "11") (pinfunction "SCK_11") (pintype "input"))
      (node (ref "IC7") (pin "11") (pinfunction "SCK_11") (pintype "input"))
    )
    (net (code "37") (name "Net-(DIN-3)") (class "Default")
      (node (ref "DIN") (pin "1") (pinfunction "3_1") (pintype "passive"))
      (node (ref "IC1") (pin "14") (pinfunction "SER_14") (pintype "input"))
    )
    (net (code "38") (name "Net-(DOUT-3)") (class "Default")
      (node (ref "DOUT") (pin "1") (pinfunction "3_1") (pintype "passive"))
      (node (ref "IC10") (pin "9") (pinfunction "QH*_9") (pintype "tri_state"))
    )
    (net (code "39") (name "Net-(GND-3)") (class "Default")
      (node (ref "C1") (pin "2") (pinfunction "2_2") (pintype "passive"))
      (node (ref "C10") (pin "2") (pinfunction "2_2") (pintype "passive"))
      (node (ref "C11") (pin "2") (pinfunction "2_2") (pintype "passive"))
      (node (ref "C12") (pin "2") (pinfunction "2_2") (pintype "passive"))
      (node (ref "C13") (pin "1") (pinfunction "1_1") (pintype "passive"))
      (node (ref "C14") (pin "1") (pinfunction "1_1") (pintype "passive"))
      (node (ref "C15") (pin "1") (pinfunction "1_1") (pintype "passive"))
      (node (ref "C16") (pin "1") (pinfunction "1_1") (pintype "passive"))
      (node (ref "C2") (pin "1") (pinfunction "1_1") (pintype "passive"))
      (node (ref "C3") (pin "2") (pinfunction "2_2") (pintype "passive"))
      (node (ref "C4") (pin "2") (pinfunction "2_2") (pintype "passive"))
      (node (ref "C5") (pin "2") (pinfunction "2_2") (pintype "passive"))
      (node (ref "C6") (pin "1") (pinfunction "1_1") (pintype "passive"))
      (node (ref "C7") (pin "1") (pinfunction "1_1") (pintype "passive"))
      (node (ref "C8") (pin "2") (pinfunction "2_2") (pintype "passive"))
      (node (ref "C9") (pin "1") (pinfunction "1_1") (pintype "passive"))
      (node (ref "GND") (pin "1") (pinfunction "3_1") (pintype "passive"))
      (node (ref "GND1") (pin "1") (pinfunction "3_1") (pintype "passive"))
      (node (ref "IC1") (pin "13") (pinfunction "G_13") (pintype "input"))
      (node (ref "IC1") (pin "8") (pinfunction "GND_8") (pintype "power_in"))
      (node (ref "IC10") (pin "13") (pinfunction "G_13") (pintype "input"))
      (node (ref "IC10") (pin "8") (pinfunction "GND_8") (pintype "power_in"))
      (node (ref "IC4") (pin "13") (pinfunction "G_13") (pintype "input"))
      (node (ref "IC4") (pin "8") (pinfunction "GND_8") (pintype "power_in"))
      (node (ref "IC7") (pin "13") (pinfunction "G_13") (pintype "input"))
      (node (ref "IC7") (pin "8") (pinfunction "GND_8") (pintype "power_in"))
    )
    (net (code "40") (name "Net-(IC1A-QA)") (class "Default")
      (node (ref "IC1") (pin "15") (pinfunction "QA_15") (pintype "tri_state"))
      (node (ref "IC2") (pin "3") (pinfunction "+IN_3") (pintype "input"))
    )
    (net (code "41") (name "Net-(IC1A-QB)") (class "Default")
      (node (ref "IC1") (pin "1") (pinfunction "QB_1") (pintype "tri_state"))
      (node (ref "IC2") (pin "5") (pinfunction "+IN_5") (pintype "input"))
    )
    (net (code "42") (name "Net-(IC1A-QC)") (class "Default")
      (node (ref "IC1") (pin "2") (pinfunction "QC_2") (pintype "tri_state"))
      (node (ref "IC2") (pin "10") (pinfunction "+IN_10") (pintype "input"))
    )
    (net (code "43") (name "Net-(IC1A-QD)") (class "Default")
      (node (ref "IC1") (pin "3") (pinfunction "QD_3") (pintype "tri_state"))
      (node (ref "IC2") (pin "12") (pinfunction "+IN_12") (pintype "input"))
    )
    (net (code "44") (name "Net-(IC1A-QE)") (class "Default")
      (node (ref "IC1") (pin "4") (pinfunction "QE_4") (pintype "tri_state"))
      (node (ref "IC3") (pin "3") (pinfunction "+IN_3") (pintype "input"))
    )
    (net (code "45") (name "Net-(IC1A-QF)") (class "Default")
      (node (ref "IC1") (pin "5") (pinfunction "QF_5") (pintype "tri_state"))
      (node (ref "IC3") (pin "5") (pinfunction "+IN_5") (pintype "input"))
    )
    (net (code "46") (name "Net-(IC1A-QG)") (class "Default")
      (node (ref "IC1") (pin "6") (pinfunction "QG_6") (pintype "tri_state"))
      (node (ref "IC3") (pin "10") (pinfunction "+IN_10") (pintype "input"))
    )
    (net (code "47") (name "Net-(IC1A-QH)") (class "Default")
      (node (ref "IC1") (pin "7") (pinfunction "QH_7") (pintype "tri_state"))
      (node (ref "IC3") (pin "12") (pinfunction "+IN_12") (pintype "input"))
    )
    (net (code "48") (name "Net-(IC1A-QH*)") (class "Default")
      (node (ref "IC1") (pin "9") (pinfunction "QH*_9") (pintype "tri_state"))
      (node (ref "IC4") (pin "14") (pinfunction "SER_14") (pintype "input"))
    )
    (net (code "49") (name "Net-(IC2A--IN)") (class "Default")
      (node (ref "IC2") (pin "1") (pinfunction "OUT_1") (pintype "output"))
      (node (ref "IC2") (pin "2") (pinfunction "-IN_2") (pintype "input"))
      (node (ref "R1") (pin "1") (pinfunction "1_1") (pintype "passive"))
    )
    (net (code "50") (name "Net-(IC2B--IN)") (class "Default")
      (node (ref "IC2") (pin "6") (pinfunction "-IN_6") (pintype "input"))
      (node (ref "IC2") (pin "7") (pinfunction "OUT_7") (pintype "output"))
      (node (ref "R2") (pin "1") (pinfunction "1_1") (pintype "passive"))
    )
    (net (code "51") (name "Net-(IC2C--IN)") (class "Default")
      (node (ref "IC2") (pin "8") (pinfunction "OUT_8") (pintype "output"))
      (node (ref "IC2") (pin "9") (pinfunction "-IN_9") (pintype "input"))
      (node (ref "R3") (pin "1") (pinfunction "1_1") (pintype "passive"))
    )
    (net (code "52") (name "Net-(IC2D--IN)") (class "Default")
      (node (ref "IC2") (pin "13") (pinfunction "-IN_13") (pintype "input"))
      (node (ref "IC2") (pin "14") (pinfunction "OUT_14") (pintype "output"))
      (node (ref "R4") (pin "1") (pinfunction "1_1") (pintype "passive"))
    )
    (net (code "53") (name "Net-(IC3A--IN)") (class "Default")
      (node (ref "IC3") (pin "1") (pinfunction "OUT_1") (pintype "output"))
      (node (ref "IC3") (pin "2") (pinfunction "-IN_2") (pintype "input"))
      (node (ref "R5") (pin "1") (pinfunction "1_1") (pintype "passive"))
    )
    (net (code "54") (name "Net-(IC3B--IN)") (class "Default")
      (node (ref "IC3") (pin "6") (pinfunction "-IN_6") (pintype "input"))
      (node (ref "IC3") (pin "7") (pinfunction "OUT_7") (pintype "output"))
      (node (ref "R6") (pin "1") (pinfunction "1_1") (pintype "passive"))
    )
    (net (code "55") (name "Net-(IC3C--IN)") (class "Default")
      (node (ref "IC3") (pin "8") (pinfunction "OUT_8") (pintype "output"))
      (node (ref "IC3") (pin "9") (pinfunction "-IN_9") (pintype "input"))
      (node (ref "R7") (pin "1") (pinfunction "1_1") (pintype "passive"))
    )
    (net (code "56") (name "Net-(IC3D--IN)") (class "Default")
      (node (ref "IC3") (pin "13") (pinfunction "-IN_13") (pintype "input"))
      (node (ref "IC3") (pin "14") (pinfunction "OUT_14") (pintype "output"))
      (node (ref "R8") (pin "1") (pinfunction "1_1") (pintype "passive"))
    )
    (net (code "57") (name "Net-(IC4A-QA)") (class "Default")
      (node (ref "IC4") (pin "15") (pinfunction "QA_15") (pintype "tri_state"))
      (node (ref "IC5") (pin "3") (pinfunction "+IN_3") (pintype "input"))
    )
    (net (code "58") (name "Net-(IC4A-QB)") (class "Default")
      (node (ref "IC4") (pin "1") (pinfunction "QB_1") (pintype "tri_state"))
      (node (ref "IC5") (pin "5") (pinfunction "+IN_5") (pintype "input"))
    )
    (net (code "59") (name "Net-(IC4A-QC)") (class "Default")
      (node (ref "IC4") (pin "2") (pinfunction "QC_2") (pintype "tri_state"))
      (node (ref "IC5") (pin "10") (pinfunction "+IN_10") (pintype "input"))
    )
    (net (code "60") (name "Net-(IC4A-QD)") (class "Default")
      (node (ref "IC4") (pin "3") (pinfunction "QD_3") (pintype "tri_state"))
      (node (ref "IC5") (pin "12") (pinfunction "+IN_12") (pintype "input"))
    )
    (net (code "61") (name "Net-(IC4A-QE)") (class "Default")
      (node (ref "IC4") (pin "4") (pinfunction "QE_4") (pintype "tri_state"))
      (node (ref "IC6") (pin "3") (pinfunction "+IN_3") (pintype "input"))
    )
    (net (code "62") (name "Net-(IC4A-QF)") (class "Default")
      (node (ref "IC4") (pin "5") (pinfunction "QF_5") (pintype "tri_state"))
      (node (ref "IC6") (pin "5") (pinfunction "+IN_5") (pintype "input"))
    )
    (net (code "63") (name "Net-(IC4A-QG)") (class "Default")
      (node (ref "IC4") (pin "6") (pinfunction "QG_6") (pintype "tri_state"))
      (node (ref "IC6") (pin "10") (pinfunction "+IN_10") (pintype "input"))
    )
    (net (code "64") (name "Net-(IC4A-QH)") (class "Default")
      (node (ref "IC4") (pin "7") (pinfunction "QH_7") (pintype "tri_state"))
      (node (ref "IC6") (pin "12") (pinfunction "+IN_12") (pintype "input"))
    )
    (net (code "65") (name "Net-(IC4A-QH*)") (class "Default")
      (node (ref "IC4") (pin "9") (pinfunction "QH*_9") (pintype "tri_state"))
      (node (ref "IC7") (pin "14") (pinfunction "SER_14") (pintype "input"))
    )
    (net (code "66") (name "Net-(IC5A--IN)") (class "Default")
      (node (ref "IC5") (pin "1") (pinfunction "OUT_1") (pintype "output"))
      (node (ref "IC5") (pin "2") (pinfunction "-IN_2") (pintype "input"))
      (node (ref "R9") (pin "1") (pinfunction "1_1") (pintype "passive"))
    )
    (net (code "67") (name "Net-(IC5B--IN)") (class "Default")
      (node (ref "IC5") (pin "6") (pinfunction "-IN_6") (pintype "input"))
      (node (ref "IC5") (pin "7") (pinfunction "OUT_7") (pintype "output"))
      (node (ref "R10") (pin "1") (pinfunction "1_1") (pintype "passive"))
    )
    (net (code "68") (name "Net-(IC5C--IN)") (class "Default")
      (node (ref "IC5") (pin "8") (pinfunction "OUT_8") (pintype "output"))
      (node (ref "IC5") (pin "9") (pinfunction "-IN_9") (pintype "input"))
      (node (ref "R11") (pin "1") (pinfunction "1_1") (pintype "passive"))
    )
    (net (code "69") (name "Net-(IC5D--IN)") (class "Default")
      (node (ref "IC5") (pin "13") (pinfunction "-IN_13") (pintype "input"))
      (node (ref "IC5") (pin "14") (pinfunction "OUT_14") (pintype "output"))
      (node (ref "R12") (pin "1") (pinfunction "1_1") (pintype "passive"))
    )
    (net (code "70") (name "Net-(IC6A--IN)") (class "Default")
      (node (ref "IC6") (pin "1") (pinfunction "OUT_1") (pintype "output"))
      (node (ref "IC6") (pin "2") (pinfunction "-IN_2") (pintype "input"))
      (node (ref "R13") (pin "1") (pinfunction "1_1") (pintype "passive"))
    )
    (net (code "71") (name "Net-(IC6B--IN)") (class "Default")
      (node (ref "IC6") (pin "6") (pinfunction "-IN_6") (pintype "input"))
      (node (ref "IC6") (pin "7") (pinfunction "OUT_7") (pintype "output"))
      (node (ref "R14") (pin "1") (pinfunction "1_1") (pintype "passive"))
    )
    (net (code "72") (name "Net-(IC6C--IN)") (class "Default")
      (node (ref "IC6") (pin "8") (pinfunction "OUT_8") (pintype "output"))
      (node (ref "IC6") (pin "9") (pinfunction "-IN_9") (pintype "input"))
      (node (ref "R15") (pin "1") (pinfunction "1_1") (pintype "passive"))
    )
    (net (code "73") (name "Net-(IC6D--IN)") (class "Default")
      (node (ref "IC6") (pin "13") (pinfunction "-IN_13") (pintype "input"))
      (node (ref "IC6") (pin "14") (pinfunction "OUT_14") (pintype "output"))
      (node (ref "R16") (pin "1") (pinfunction "1_1") (pintype "passive"))
    )
    (net (code "74") (name "Net-(IC7A-QA)") (class "Default")
      (node (ref "IC7") (pin "15") (pinfunction "QA_15") (pintype "tri_state"))
      (node (ref "IC8") (pin "3") (pinfunction "+IN_3") (pintype "input"))
    )
    (net (code "75") (name "Net-(IC7A-QB)") (class "Default")
      (node (ref "IC7") (pin "1") (pinfunction "QB_1") (pintype "tri_state"))
      (node (ref "IC8") (pin "5") (pinfunction "+IN_5") (pintype "input"))
    )
    (net (code "76") (name "Net-(IC7A-QC)") (class "Default")
      (node (ref "IC7") (pin "2") (pinfunction "QC_2") (pintype "tri_state"))
      (node (ref "IC8") (pin "10") (pinfunction "+IN_10") (pintype "input"))
    )
    (net (code "77") (name "Net-(IC7A-QD)") (class "Default")
      (node (ref "IC7") (pin "3") (pinfunction "QD_3") (pintype "tri_state"))
      (node (ref "IC8") (pin "12") (pinfunction "+IN_12") (pintype "input"))
    )
    (net (code "78") (name "Net-(IC7A-QE)") (class "Default")
      (node (ref "IC7") (pin "4") (pinfunction "QE_4") (pintype "tri_state"))
      (node (ref "IC9") (pin "3") (pinfunction "+IN_3") (pintype "input"))
    )
    (net (code "79") (name "Net-(IC7A-QF)") (class "Default")
      (node (ref "IC7") (pin "5") (pinfunction "QF_5") (pintype "tri_state"))
      (node (ref "IC9") (pin "5") (pinfunction "+IN_5") (pintype "input"))
    )
    (net (code "80") (name "Net-(IC7A-QG)") (class "Default")
      (node (ref "IC7") (pin "6") (pinfunction "QG_6") (pintype "tri_state"))
      (node (ref "IC9") (pin "10") (pinfunction "+IN_10") (pintype "input"))
    )
    (net (code "81") (name "Net-(IC7A-QH)") (class "Default")
      (node (ref "IC7") (pin "7") (pinfunction "QH_7") (pintype "tri_state"))
      (node (ref "IC9") (pin "12") (pinfunction "+IN_12") (pintype "input"))
    )
    (net (code "82") (name "Net-(IC8A--IN)") (class "Default")
      (node (ref "IC8") (pin "1") (pinfunction "OUT_1") (pintype "output"))
      (node (ref "IC8") (pin "2") (pinfunction "-IN_2") (pintype "input"))
      (node (ref "R17") (pin "1") (pinfunction "1_1") (pintype "passive"))
    )
    (net (code "83") (name "Net-(IC8B--IN)") (class "Default")
      (node (ref "IC8") (pin "6") (pinfunction "-IN_6") (pintype "input"))
      (node (ref "IC8") (pin "7") (pinfunction "OUT_7") (pintype "output"))
      (node (ref "R18") (pin "1") (pinfunction "1_1") (pintype "passive"))
    )
    (net (code "84") (name "Net-(IC8C--IN)") (class "Default")
      (node (ref "IC8") (pin "8") (pinfunction "OUT_8") (pintype "output"))
      (node (ref "IC8") (pin "9") (pinfunction "-IN_9") (pintype "input"))
      (node (ref "R19") (pin "1") (pinfunction "1_1") (pintype "passive"))
    )
    (net (code "85") (name "Net-(IC8D--IN)") (class "Default")
      (node (ref "IC8") (pin "13") (pinfunction "-IN_13") (pintype "input"))
      (node (ref "IC8") (pin "14") (pinfunction "OUT_14") (pintype "output"))
      (node (ref "R20") (pin "1") (pinfunction "1_1") (pintype "passive"))
    )
    (net (code "86") (name "Net-(IC9A--IN)") (class "Default")
      (node (ref "IC9") (pin "1") (pinfunction "OUT_1") (pintype "output"))
      (node (ref "IC9") (pin "2") (pinfunction "-IN_2") (pintype "input"))
      (node (ref "R21") (pin "1") (pinfunction "1_1") (pintype "passive"))
    )
    (net (code "87") (name "Net-(IC9B--IN)") (class "Default")
      (node (ref "IC9") (pin "6") (pinfunction "-IN_6") (pintype "input"))
      (node (ref "IC9") (pin "7") (pinfunction "OUT_7") (pintype "output"))
      (node (ref "R22") (pin "1") (pinfunction "1_1") (pintype "passive"))
    )
    (net (code "88") (name "Net-(IC9C--IN)") (class "Default")
      (node (ref "IC9") (pin "8") (pinfunction "OUT_8") (pintype "output"))
      (node (ref "IC9") (pin "9") (pinfunction "-IN_9") (pintype "input"))
      (node (ref "R23") (pin "1") (pinfunction "1_1") (pintype "passive"))
    )
    (net (code "89") (name "Net-(IC9D--IN)") (class "Default")
      (node (ref "IC9") (pin "13") (pinfunction "-IN_13") (pintype "input"))
      (node (ref "IC9") (pin "14") (pinfunction "OUT_14") (pintype "output"))
      (node (ref "R24") (pin "1") (pinfunction "1_1") (pintype "passive"))
    )
    (net (code "90") (name "Net-(IC10A-QA)") (class "Default")
      (node (ref "IC10") (pin "15") (pinfunction "QA_15") (pintype "tri_state"))
      (node (ref "IC11") (pin "3") (pinfunction "+IN_3") (pintype "input"))
    )
    (net (code "91") (name "Net-(IC10A-QB)") (class "Default")
      (node (ref "IC10") (pin "1") (pinfunction "QB_1") (pintype "tri_state"))
      (node (ref "IC11") (pin "5") (pinfunction "+IN_5") (pintype "input"))
    )
    (net (code "92") (name "Net-(IC10A-QC)") (class "Default")
      (node (ref "IC10") (pin "2") (pinfunction "QC_2") (pintype "tri_state"))
      (node (ref "IC11") (pin "10") (pinfunction "+IN_10") (pintype "input"))
    )
    (net (code "93") (name "Net-(IC10A-QD)") (class "Default")
      (node (ref "IC10") (pin "3") (pinfunction "QD_3") (pintype "tri_state"))
      (node (ref "IC11") (pin "12") (pinfunction "+IN_12") (pintype "input"))
    )
    (net (code "94") (name "Net-(IC10A-QE)") (class "Default")
      (node (ref "IC10") (pin "4") (pinfunction "QE_4") (pintype "tri_state"))
      (node (ref "IC12") (pin "3") (pinfunction "+IN_3") (pintype "input"))
    )
    (net (code "95") (name "Net-(IC10A-QF)") (class "Default")
      (node (ref "IC10") (pin "5") (pinfunction "QF_5") (pintype "tri_state"))
      (node (ref "IC12") (pin "5") (pinfunction "+IN_5") (pintype "input"))
    )
    (net (code "96") (name "Net-(IC10A-QG)") (class "Default")
      (node (ref "IC10") (pin "6") (pinfunction "QG_6") (pintype "tri_state"))
      (node (ref "IC12") (pin "10") (pinfunction "+IN_10") (pintype "input"))
    )
    (net (code "97") (name "Net-(IC10A-QH)") (class "Default")
      (node (ref "IC10") (pin "7") (pinfunction "QH_7") (pintype "tri_state"))
      (node (ref "IC12") (pin "12") (pinfunction "+IN_12") (pintype "input"))
    )
    (net (code "98") (name "Net-(IC10A-RCK)") (class "Default")
      (node (ref "IC1") (pin "12") (pinfunction "RCK_12") (pintype "input"))
      (node (ref "IC10") (pin "12") (pinfunction "RCK_12") (pintype "input"))
      (node (ref "IC4") (pin "12") (pinfunction "RCK_12") (pintype "input"))
      (node (ref "IC7") (pin "12") (pinfunction "RCK_12") (pintype "input"))
      (node (ref "LATCH") (pin "1") (pinfunction "3_1") (pintype "passive"))
      (node (ref "LATCH2") (pin "1") (pinfunction "3_1") (pintype "passive"))
    )
    (net (code "99") (name "Net-(IC10A-SER)") (class "Default")
      (node (ref "IC10") (pin "14") (pinfunction "SER_14") (pintype "input"))
      (node (ref "IC7") (pin "9") (pinfunction "QH*_9") (pintype "tri_state"))
    )
    (net (code "100") (name "Net-(IC11A--IN)") (class "Default")
      (node (ref "IC11") (pin "1") (pinfunction "OUT_1") (pintype "output"))
      (node (ref "IC11") (pin "2") (pinfunction "-IN_2") (pintype "input"))
      (node (ref "R25") (pin "1") (pinfunction "1_1") (pintype "passive"))
    )
    (net (code "101") (name "Net-(IC11B--IN)") (class "Default")
      (node (ref "IC11") (pin "6") (pinfunction "-IN_6") (pintype "input"))
      (node (ref "IC11") (pin "7") (pinfunction "OUT_7") (pintype "output"))
      (node (ref "R26") (pin "1") (pinfunction "1_1") (pintype "passive"))
    )
    (net (code "102") (name "Net-(IC11C--IN)") (class "Default")
      (node (ref "IC11") (pin "8") (pinfunction "OUT_8") (pintype "output"))
      (node (ref "IC11") (pin "9") (pinfunction "-IN_9") (pintype "input"))
      (node (ref "R27") (pin "1") (pinfunction "1_1") (pintype "passive"))
    )
    (net (code "103") (name "Net-(IC11D--IN)") (class "Default")
      (node (ref "IC11") (pin "13") (pinfunction "-IN_13") (pintype "input"))
      (node (ref "IC11") (pin "14") (pinfunction "OUT_14") (pintype "output"))
      (node (ref "R28") (pin "1") (pinfunction "1_1") (pintype "passive"))
    )
    (net (code "104") (name "Net-(IC12A--IN)") (class "Default")
      (node (ref "IC12") (pin "1") (pinfunction "OUT_1") (pintype "output"))
      (node (ref "IC12") (pin "2") (pinfunction "-IN_2") (pintype "input"))
      (node (ref "R29") (pin "1") (pinfunction "1_1") (pintype "passive"))
    )
    (net (code "105") (name "Net-(IC12B--IN)") (class "Default")
      (node (ref "IC12") (pin "6") (pinfunction "-IN_6") (pintype "input"))
      (node (ref "IC12") (pin "7") (pinfunction "OUT_7") (pintype "output"))
      (node (ref "R30") (pin "1") (pinfunction "1_1") (pintype "passive"))
    )
    (net (code "106") (name "Net-(IC12C--IN)") (class "Default")
      (node (ref "IC12") (pin "8") (pinfunction "OUT_8") (pintype "output"))
      (node (ref "IC12") (pin "9") (pinfunction "-IN_9") (pintype "input"))
      (node (ref "R31") (pin "1") (pinfunction "1_1") (pintype "passive"))
    )
    (net (code "107") (name "Net-(IC12D--IN)") (class "Default")
      (node (ref "IC12") (pin "13") (pinfunction "-IN_13") (pintype "input"))
      (node (ref "IC12") (pin "14") (pinfunction "OUT_14") (pintype "output"))
      (node (ref "R32") (pin "1") (pinfunction "1_1") (pintype "passive"))
    )
  )
)
